# 10_-_Isolation.net
KiCad netlist of a schematic drawn in Altium Designer
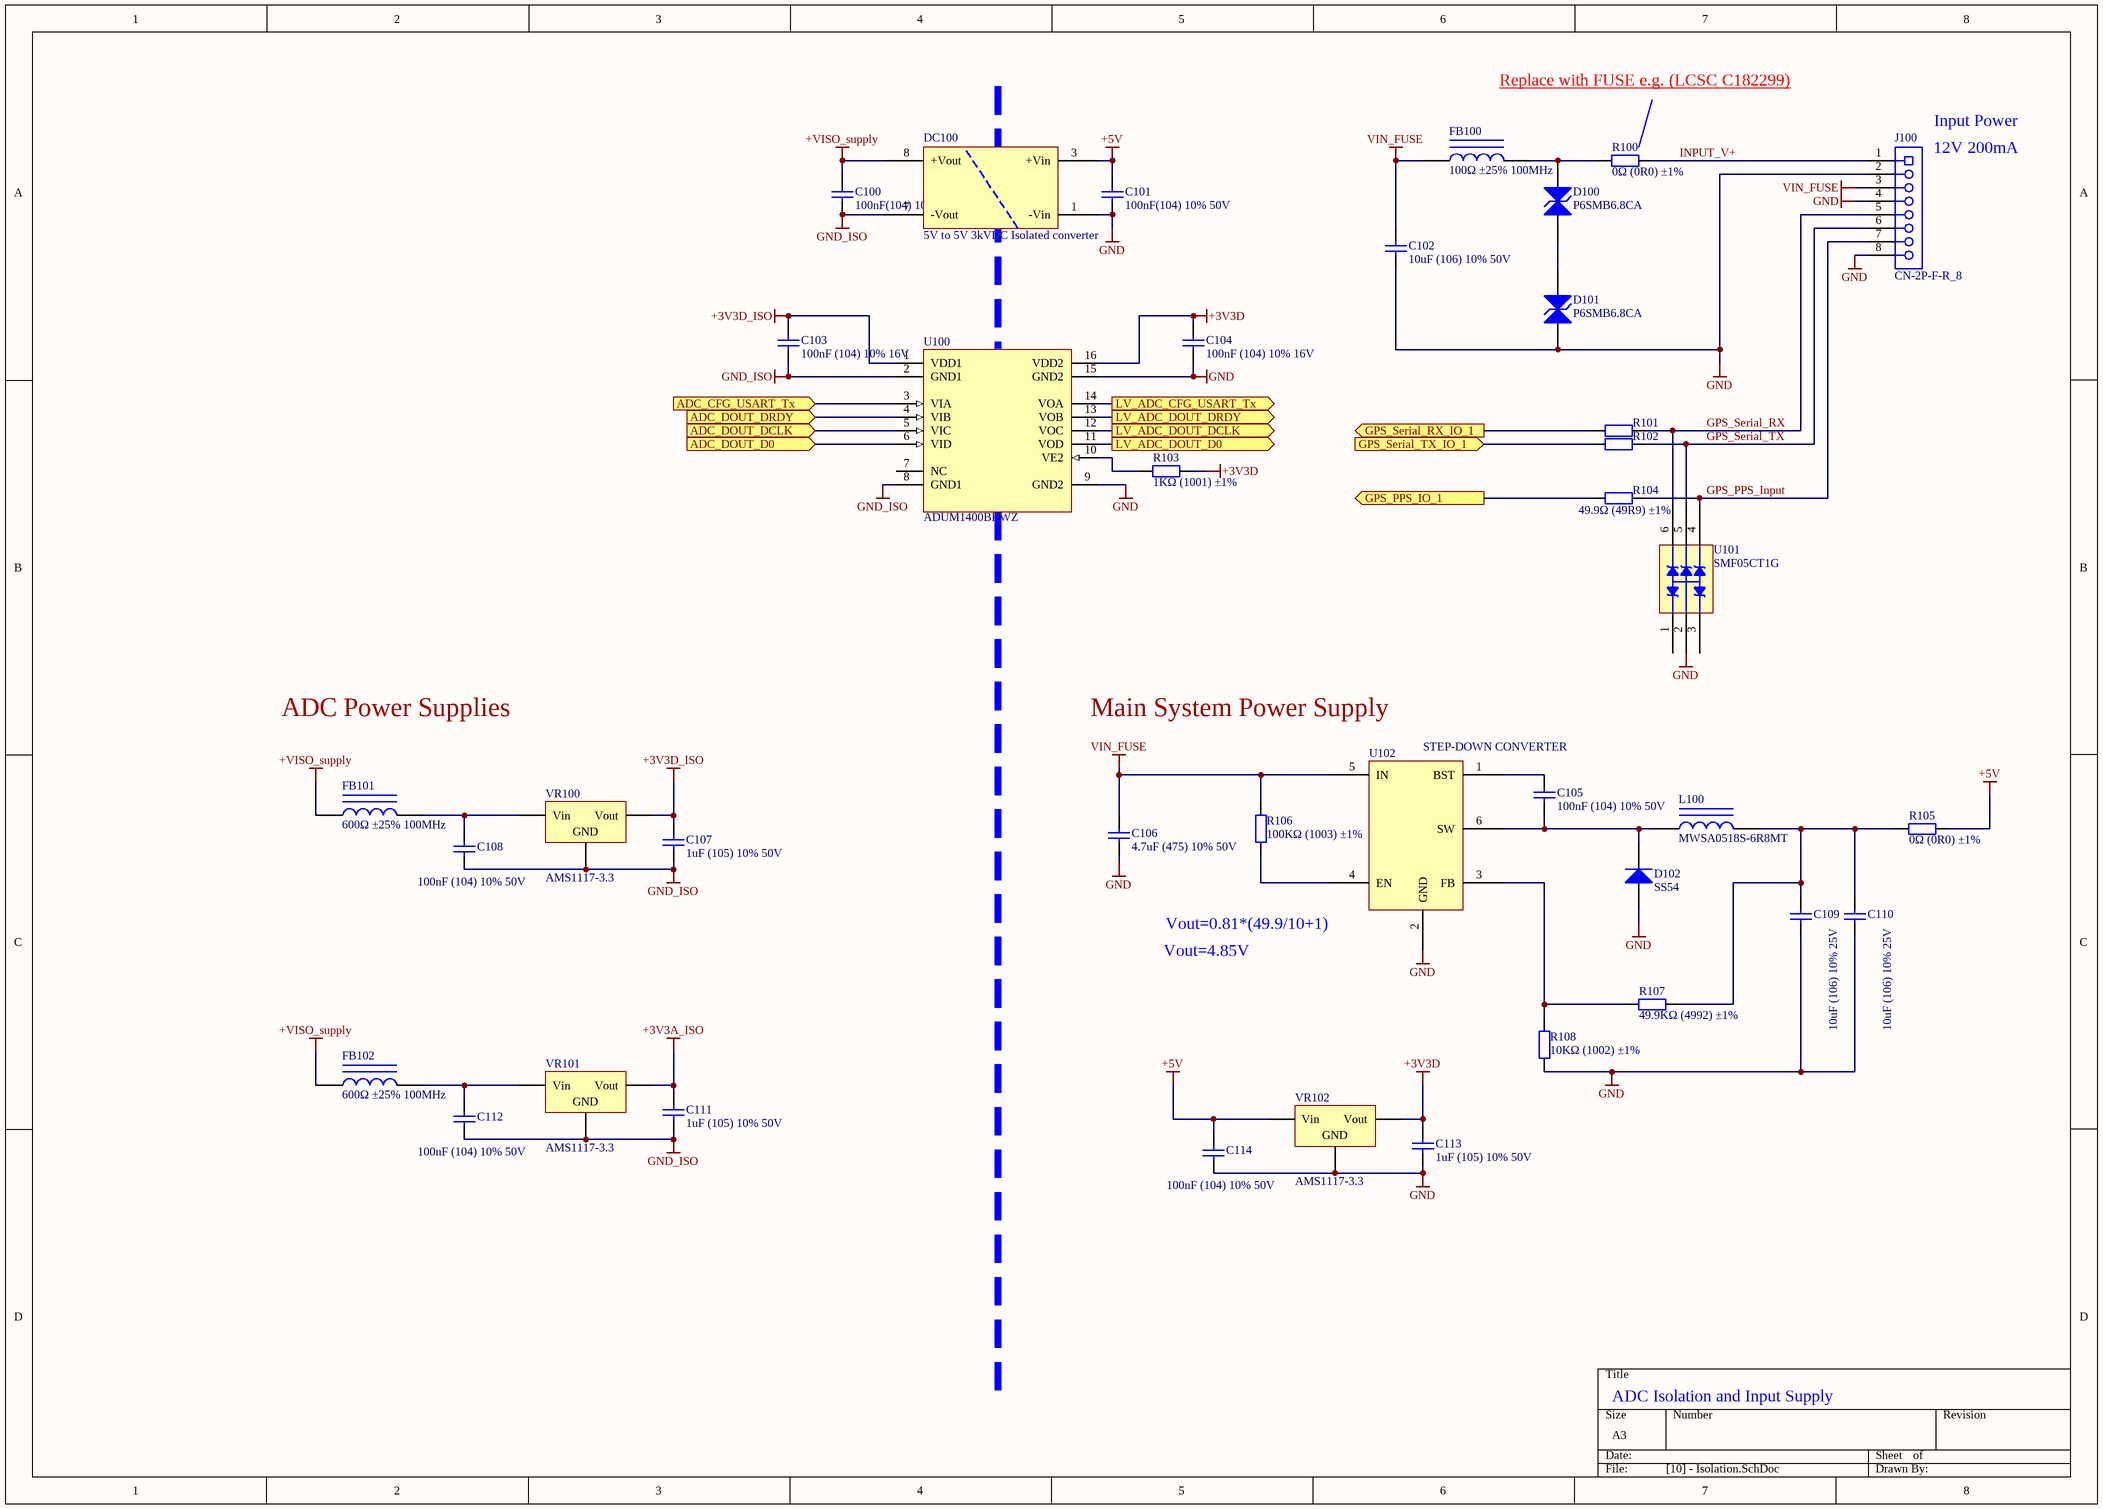
[diagram p0: [10] - Isolation.SchDoc]

(export (version "E")
  (design (tool "Eeschema 10.0.6"))
  (components
    (comp (ref "C100")
      (value "100nF(104) 10% 50V")
      (footprint "0805_C")
      (description "贴片电容")
      (libsource (lib "Cap") (part "0805 100nF(104) 10% 50V"))
    )
    (comp (ref "C101")
      (value "100nF(104) 10% 50V")
      (footprint "0805_C")
      (description "贴片电容")
      (libsource (lib "Cap") (part "0805 100nF(104) 10% 50V"))
    )
    (comp (ref "C102")
      (value "10uF (106) 10% 50V")
      (footprint "1206_C")
      (description "贴片电容")
      (libsource (lib "Cap") (part "1206 10uF (106) 10% 50V"))
    )
    (comp (ref "C103")
      (value "100nF (104) 10% 16V")
      (footprint "0402_C")
      (description "贴片电容")
      (libsource (lib "Cap") (part "0402 100nF (104) 10% 16V"))
    )
    (comp (ref "C104")
      (value "100nF (104) 10% 16V")
      (footprint "0402_C")
      (description "贴片电容")
      (libsource (lib "Cap") (part "0402 100nF (104) 10% 16V"))
    )
    (comp (ref "C105")
      (value "100nF (104) 10% 50V")
      (footprint "0603_C")
      (description "贴片电容")
      (libsource (lib "Cap") (part "0603 100nF (104) 10% 50V"))
    )
    (comp (ref "C106")
      (value "4.7uF (475) 10% 50V")
      (footprint "1206_C")
      (description "贴片电容")
      (libsource (lib "Cap") (part "1206 4.7uF (475) 10% 50V"))
    )
    (comp (ref "C107")
      (value "1uF (105) 10% 50V")
      (footprint "0603_C")
      (description "贴片电容")
      (libsource (lib "Cap") (part "0603 1uF (105) 10% 50V"))
    )
    (comp (ref "C108")
      (value "100nF (104) 10% 50V")
      (footprint "0603_C")
      (description "贴片电容")
      (libsource (lib "Cap") (part "0603 100nF (104) 10% 50V"))
    )
    (comp (ref "C109")
      (value "10uF (106) 10% 25V")
      (footprint "0805_C")
      (description "贴片电容")
      (libsource (lib "Cap") (part "0805 10uF (106) 10% 25V"))
    )
    (comp (ref "C110")
      (value "10uF (106) 10% 25V")
      (footprint "0805_C")
      (description "贴片电容")
      (libsource (lib "Cap") (part "0805 10uF (106) 10% 25V"))
    )
    (comp (ref "C111")
      (value "1uF (105) 10% 50V")
      (footprint "0603_C")
      (description "贴片电容")
      (libsource (lib "Cap") (part "0603 1uF (105) 10% 50V"))
    )
    (comp (ref "C112")
      (value "100nF (104) 10% 50V")
      (footprint "0603_C")
      (description "贴片电容")
      (libsource (lib "Cap") (part "0603 100nF (104) 10% 50V"))
    )
    (comp (ref "C113")
      (value "1uF (105) 10% 50V")
      (footprint "0603_C")
      (description "贴片电容")
      (libsource (lib "Cap") (part "0603 1uF (105) 10% 50V"))
    )
    (comp (ref "C114")
      (value "100nF (104) 10% 50V")
      (footprint "0603_C")
      (description "贴片电容")
      (libsource (lib "Cap") (part "0603 100nF (104) 10% 50V"))
    )
    (comp (ref "D100")
      (value "P6SMB6.8CA")
      (footprint "SMB(DO-214AA)_S1")
      (description "TVS")
      (libsource (lib "Diode") (part "SMB/DO-214AA P6SMB6.8CA"))
    )
    (comp (ref "D101")
      (value "P6SMB6.8CA")
      (footprint "SMB(DO-214AA)_S1")
      (description "TVS")
      (libsource (lib "Diode") (part "SMB/DO-214AA P6SMB6.8CA"))
    )
    (comp (ref "D102")
      (value "SS54")
      (footprint "SMA(DO-214AC)_S1")
      (description "二极管")
      (libsource (lib "Diode") (part "SMA(DO-214AC) SS54"))
    )
    (comp (ref "DC100")
      (value "5V to 5V 3kVDC Isolated converter")
      (footprint "NXE1S0505MC-R7")
      (description "NXE1 1W Isolated DC-DC Converter Surface Mount, Voltage in 4.5 → 5.5 V dc")
      (libsource (lib "FPGA_PMU_lib") (part "NXE1S0505MC-R7"))
    )
    (comp (ref "FB100")
      (value "100Ω ±25% 100MHz")
      (footprint "0805_L")
      (description "贴片磁珠")
      (libsource (lib "IUD") (part "0805 100Ω 25% 100MHz"))
    )
    (comp (ref "FB101")
      (value "600Ω ±25% 100MHz")
      (footprint "0805_L")
      (description "贴片磁珠")
      (libsource (lib "IUD") (part "0805 600Ω 25% 100MHz"))
    )
    (comp (ref "FB102")
      (value "600Ω ±25% 100MHz")
      (footprint "0805_L")
      (description "贴片磁珠")
      (libsource (lib "IUD") (part "0805 600Ω 25% 100MHz"))
    )
    (comp (ref "J100")
      (value "CN-2P-F-R_8")
      (footprint "PHOE-8way")
      (description "8way - 5.08 block")
      (libsource (lib "xPMU_lib") (part "CN-2P-F-R_8"))
    )
    (comp (ref "L100")
      (value "MWSA0518S-6R8MT")
      (footprint "MWSA0518")
      (description "POWER INDUCTORS SMD,5.2X5.4X1.8MM ROHS")
      (libsource (lib "FPGA_PMU_lib") (part "MWSA0518S-6R8MT"))
    )
    (comp (ref "R100")
      (value "0Ω (0R0) ±1%")
      (footprint "0603_R")
      (description "贴片电阻")
      (libsource (lib "RES") (part "0603 0Ω (0R0) 1%"))
    )
    (comp (ref "R101")
      (value "49.9Ω (49R9) ±1%")
      (footprint "0402_R")
      (description "贴片电阻")
      (libsource (lib "RES") (part "0402 49.9Ω (49R9) 1%"))
    )
    (comp (ref "R102")
      (value "49.9Ω (49R9) ±1%")
      (footprint "0402_R")
      (description "贴片电阻")
      (libsource (lib "RES") (part "0402 49.9Ω (49R9) 1%"))
    )
    (comp (ref "R103")
      (value "1KΩ (1001) ±1%")
      (footprint "0402_R")
      (description "贴片电阻")
      (libsource (lib "RES") (part "0402 1KΩ (1001) 1%"))
    )
    (comp (ref "R104")
      (value "49.9Ω (49R9) ±1%")
      (footprint "0402_R")
      (description "贴片电阻")
      (libsource (lib "RES") (part "0402 49.9Ω (49R9) 1%"))
    )
    (comp (ref "R105")
      (value "0Ω (0R0) ±1%")
      (footprint "0805_R")
      (description "贴片电阻")
      (libsource (lib "RES") (part "0805 0Ω (0R0) 1%"))
    )
    (comp (ref "R106")
      (value "100KΩ (1003) ±1%")
      (footprint "0402_R")
      (description "贴片电阻")
      (libsource (lib "RES") (part "0402 100KΩ (1003) 1%"))
    )
    (comp (ref "R107")
      (value "49.9KΩ (4992) ±1%")
      (footprint "0402_R")
      (description "贴片电阻")
      (libsource (lib "RES") (part "0402 49.9KΩ (4992) 1%"))
    )
    (comp (ref "R108")
      (value "10KΩ (1002) ±1%")
      (footprint "0402_R")
      (description "贴片电阻")
      (libsource (lib "RES") (part "0402 10KΩ (1002) 1%"))
    )
    (comp (ref "U100")
      (value "ADUM1400BRWZ")
      (footprint "ADI-RW-16_L")
      (fields (field (name "MANUFACTURER") "Analog Devices"))
      (libsource (lib "FPGA_PMU_lib") (part "ADI-ADUMX400-RX-16"))
    )
    (comp (ref "U101")
      (value "SMF05CT1G")
      (footprint "SC-70-6(SOT-363)")
      (description "TVS")
      (libsource (lib "IC") (part "SMF05CT1G_[C15879]"))
    )
    (comp (ref "U102")
      (value "STEP-DOWN CONVERTER")
      (footprint "*TSOT-23_S6")
      (description "1.2A, 24V, 1.4MHz STEP-DOWN CONVERTER IN A TSOT23-6")
      (libsource (lib "FPGA_PMU_lib") (part "MP2359"))
    )
    (comp (ref "VR100")
      (value "AMS1117-3.3")
      (footprint "SOT-223")
      (description "低压差线性稳压(LDO)")
      (libsource (lib "LDO") (part "SOT-223 AMS1117-3.3"))
    )
    (comp (ref "VR101")
      (value "AMS1117-3.3")
      (footprint "SOT-223")
      (description "低压差线性稳压(LDO)")
      (libsource (lib "LDO") (part "SOT-223 AMS1117-3.3"))
    )
    (comp (ref "VR102")
      (value "AMS1117-3.3")
      (footprint "SOT-223")
      (description "低压差线性稳压(LDO)")
      (libsource (lib "LDO") (part "SOT-223 AMS1117-3.3"))
    )
  )
  (nets
    (net (code "1") (name "+3V3A_ISO") (class "Default")
      (node (ref "C111") (pin "2") (pinfunction "2_2") (pintype "passive"))
      (node (ref "VR101") (pin "2") (pinfunction "Vout_2") (pintype "passive"))
    )
    (net (code "2") (name "+3V3D") (class "Default")
      (node (ref "C104") (pin "2") (pinfunction "2_2") (pintype "passive"))
      (node (ref "C113") (pin "2") (pinfunction "2_2") (pintype "passive"))
      (node (ref "R103") (pin "2") (pinfunction "2_2") (pintype "passive"))
      (node (ref "U100") (pin "16") (pinfunction "VDD2_16") (pintype "power_in"))
      (node (ref "VR102") (pin "2") (pinfunction "Vout_2") (pintype "passive"))
    )
    (net (code "3") (name "+3V3D_ISO") (class "Default")
      (node (ref "C103") (pin "2") (pinfunction "2_2") (pintype "passive"))
      (node (ref "C107") (pin "2") (pinfunction "2_2") (pintype "passive"))
      (node (ref "U100") (pin "1") (pinfunction "VDD1_1") (pintype "power_in"))
      (node (ref "VR100") (pin "2") (pinfunction "Vout_2") (pintype "passive"))
    )
    (net (code "4") (name "+5V") (class "Default")
      (node (ref "C101") (pin "2") (pinfunction "2_2") (pintype "passive"))
      (node (ref "C114") (pin "2") (pinfunction "2_2") (pintype "passive"))
      (node (ref "DC100") (pin "3") (pinfunction "+Vin_3") (pintype "passive"))
      (node (ref "R105") (pin "2") (pinfunction "2_2") (pintype "passive"))
      (node (ref "VR102") (pin "3") (pinfunction "Vin_3") (pintype "passive"))
    )
    (net (code "5") (name "+VISO_supply") (class "Default")
      (node (ref "C100") (pin "2") (pinfunction "2_2") (pintype "passive"))
      (node (ref "DC100") (pin "8") (pinfunction "+Vout_8") (pintype "passive"))
      (node (ref "FB101") (pin "1") (pinfunction "1_1") (pintype "passive"))
      (node (ref "FB102") (pin "1") (pinfunction "1_1") (pintype "passive"))
    )
    (net (code "6") (name "/ADC_CFG_USART_Tx") (class "Default")
      (node (ref "U100") (pin "3") (pinfunction "VIA_3") (pintype "input"))
    )
    (net (code "7") (name "/ADC_DOUT_D0") (class "Default")
      (node (ref "U100") (pin "6") (pinfunction "VID_6") (pintype "input"))
    )
    (net (code "8") (name "/ADC_DOUT_DCLK") (class "Default")
      (node (ref "U100") (pin "5") (pinfunction "VIC_5") (pintype "input"))
    )
    (net (code "9") (name "/ADC_DOUT_DRDY") (class "Default")
      (node (ref "U100") (pin "4") (pinfunction "VIB_4") (pintype "input"))
    )
    (net (code "10") (name "/GPS_PPS_IO_1") (class "Default")
      (node (ref "R104") (pin "1") (pinfunction "1_1") (pintype "passive"))
    )
    (net (code "11") (name "/GPS_PPS_Input") (class "Default")
      (node (ref "J100") (pin "7") (pinfunction "7_7") (pintype "passive"))
      (node (ref "R104") (pin "2") (pinfunction "2_2") (pintype "passive"))
      (node (ref "U101") (pin "4") (pinfunction "4_4") (pintype "passive"))
    )
    (net (code "12") (name "/GPS_Serial_RX") (class "Default")
      (node (ref "J100") (pin "5") (pinfunction "5_5") (pintype "passive"))
      (node (ref "R101") (pin "2") (pinfunction "2_2") (pintype "passive"))
      (node (ref "U101") (pin "6") (pinfunction "6_6") (pintype "passive"))
    )
    (net (code "13") (name "/GPS_Serial_RX_IO_1") (class "Default")
      (node (ref "R101") (pin "1") (pinfunction "1_1") (pintype "passive"))
    )
    (net (code "14") (name "/GPS_Serial_TX") (class "Default")
      (node (ref "J100") (pin "6") (pinfunction "6_6") (pintype "passive"))
      (node (ref "R102") (pin "2") (pinfunction "2_2") (pintype "passive"))
      (node (ref "U101") (pin "5") (pinfunction "5_5") (pintype "passive"))
    )
    (net (code "15") (name "/GPS_Serial_TX_IO_1") (class "Default")
      (node (ref "R102") (pin "1") (pinfunction "1_1") (pintype "passive"))
    )
    (net (code "16") (name "/INPUT_V+") (class "Default")
      (node (ref "J100") (pin "1") (pinfunction "1_1") (pintype "passive"))
      (node (ref "R100") (pin "2") (pinfunction "2_2") (pintype "passive"))
    )
    (net (code "17") (name "/LV_ADC_CFG_USART_Tx") (class "Default")
      (node (ref "U100") (pin "14") (pinfunction "VOA_14") (pintype "tri_state"))
    )
    (net (code "18") (name "/LV_ADC_DOUT_D0") (class "Default")
      (node (ref "U100") (pin "11") (pinfunction "VOD_11") (pintype "tri_state"))
    )
    (net (code "19") (name "/LV_ADC_DOUT_DCLK") (class "Default")
      (node (ref "U100") (pin "12") (pinfunction "VOC_12") (pintype "tri_state"))
    )
    (net (code "20") (name "/LV_ADC_DOUT_DRDY") (class "Default")
      (node (ref "U100") (pin "13") (pinfunction "VOB_13") (pintype "tri_state"))
    )
    (net (code "21") (name "GND") (class "Default")
      (node (ref "C101") (pin "1") (pinfunction "1_1") (pintype "passive"))
      (node (ref "C102") (pin "1") (pinfunction "1_1") (pintype "passive"))
      (node (ref "C104") (pin "1") (pinfunction "1_1") (pintype "passive"))
      (node (ref "C106") (pin "1") (pinfunction "1_1") (pintype "passive"))
      (node (ref "C109") (pin "1") (pinfunction "1_1") (pintype "passive"))
      (node (ref "C110") (pin "1") (pinfunction "1_1") (pintype "passive"))
      (node (ref "C113") (pin "1") (pinfunction "1_1") (pintype "passive"))
      (node (ref "C114") (pin "1") (pinfunction "1_1") (pintype "passive"))
      (node (ref "D101") (pin "1") (pinfunction "A_1") (pintype "passive"))
      (node (ref "D102") (pin "1") (pinfunction "A_1") (pintype "passive"))
      (node (ref "DC100") (pin "1") (pinfunction "-Vin_1") (pintype "passive"))
      (node (ref "J100") (pin "2") (pinfunction "2_2") (pintype "passive"))
      (node (ref "J100") (pin "4") (pinfunction "4_4") (pintype "passive"))
      (node (ref "J100") (pin "8") (pinfunction "8_8") (pintype "passive"))
      (node (ref "R108") (pin "2") (pinfunction "2_2") (pintype "passive"))
      (node (ref "U100") (pin "15") (pinfunction "GND2_15") (pintype "power_in"))
      (node (ref "U100") (pin "9") (pinfunction "GND2_9") (pintype "power_in"))
      (node (ref "U101") (pin "2") (pinfunction "2_2") (pintype "passive"))
      (node (ref "U102") (pin "2") (pinfunction "GND_2") (pintype "passive"))
      (node (ref "VR102") (pin "1") (pinfunction "GND_1") (pintype "passive"))
    )
    (net (code "22") (name "GND_ISO") (class "Default")
      (node (ref "C100") (pin "1") (pinfunction "1_1") (pintype "passive"))
      (node (ref "C103") (pin "1") (pinfunction "1_1") (pintype "passive"))
      (node (ref "C107") (pin "1") (pinfunction "1_1") (pintype "passive"))
      (node (ref "C108") (pin "1") (pinfunction "1_1") (pintype "passive"))
      (node (ref "C111") (pin "1") (pinfunction "1_1") (pintype "passive"))
      (node (ref "C112") (pin "1") (pinfunction "1_1") (pintype "passive"))
      (node (ref "DC100") (pin "7") (pinfunction "-Vout_7") (pintype "passive"))
      (node (ref "U100") (pin "2") (pinfunction "GND1_2") (pintype "power_in"))
      (node (ref "U100") (pin "8") (pinfunction "GND1_8") (pintype "power_in"))
      (node (ref "VR100") (pin "1") (pinfunction "GND_1") (pintype "passive"))
      (node (ref "VR101") (pin "1") (pinfunction "GND_1") (pintype "passive"))
    )
    (net (code "23") (name "Net-(C109-Pad2)") (class "Default")
      (node (ref "C109") (pin "2") (pinfunction "2_2") (pintype "passive"))
      (node (ref "C110") (pin "2") (pinfunction "2_2") (pintype "passive"))
      (node (ref "L100") (pin "2") (pinfunction "2_2") (pintype "power_in"))
      (node (ref "R105") (pin "1") (pinfunction "1_1") (pintype "passive"))
      (node (ref "R107") (pin "2") (pinfunction "2_2") (pintype "passive"))
    )
    (net (code "24") (name "Net-(D100-A)") (class "Default")
      (node (ref "D100") (pin "1") (pinfunction "A_1") (pintype "passive"))
      (node (ref "D101") (pin "2") (pinfunction "K_2") (pintype "passive"))
    )
    (net (code "25") (name "Net-(D100-K)") (class "Default")
      (node (ref "D100") (pin "2") (pinfunction "K_2") (pintype "passive"))
      (node (ref "FB100") (pin "2") (pinfunction "2_2") (pintype "passive"))
      (node (ref "R100") (pin "1") (pinfunction "1_1") (pintype "passive"))
    )
    (net (code "26") (name "Net-(D102-K)") (class "Default")
      (node (ref "C105") (pin "1") (pinfunction "1_1") (pintype "passive"))
      (node (ref "D102") (pin "2") (pinfunction "K_2") (pintype "passive"))
      (node (ref "L100") (pin "1") (pinfunction "1_1") (pintype "power_in"))
      (node (ref "U102") (pin "6") (pinfunction "SW_6") (pintype "passive"))
    )
    (net (code "27") (name "Net-(U100-VE2)") (class "Default")
      (node (ref "R103") (pin "1") (pinfunction "1_1") (pintype "passive"))
      (node (ref "U100") (pin "10") (pinfunction "VE2_10") (pintype "input"))
    )
    (net (code "28") (name "Net-(U102-BST)") (class "Default")
      (node (ref "C105") (pin "2") (pinfunction "2_2") (pintype "passive"))
      (node (ref "U102") (pin "1") (pinfunction "BST_1") (pintype "passive"))
    )
    (net (code "29") (name "Net-(U102-EN)") (class "Default")
      (node (ref "R106") (pin "1") (pinfunction "1_1") (pintype "passive"))
      (node (ref "U102") (pin "4") (pinfunction "EN_4") (pintype "passive"))
    )
    (net (code "30") (name "Net-(U102-FB)") (class "Default")
      (node (ref "R107") (pin "1") (pinfunction "1_1") (pintype "passive"))
      (node (ref "R108") (pin "1") (pinfunction "1_1") (pintype "passive"))
      (node (ref "U102") (pin "3") (pinfunction "FB_3") (pintype "passive"))
    )
    (net (code "31") (name "Net-(VR100-Vin)") (class "Default")
      (node (ref "C108") (pin "2") (pinfunction "2_2") (pintype "passive"))
      (node (ref "FB101") (pin "2") (pinfunction "2_2") (pintype "passive"))
      (node (ref "VR100") (pin "3") (pinfunction "Vin_3") (pintype "passive"))
    )
    (net (code "32") (name "Net-(VR101-Vin)") (class "Default")
      (node (ref "C112") (pin "2") (pinfunction "2_2") (pintype "passive"))
      (node (ref "FB102") (pin "2") (pinfunction "2_2") (pintype "passive"))
      (node (ref "VR101") (pin "3") (pinfunction "Vin_3") (pintype "passive"))
    )
    (net (code "33") (name "VIN_FUSE") (class "Default")
      (node (ref "C102") (pin "2") (pinfunction "2_2") (pintype "passive"))
      (node (ref "C106") (pin "2") (pinfunction "2_2") (pintype "passive"))
      (node (ref "FB100") (pin "1") (pinfunction "1_1") (pintype "passive"))
      (node (ref "J100") (pin "3") (pinfunction "3_3") (pintype "passive"))
      (node (ref "R106") (pin "2") (pinfunction "2_2") (pintype "passive"))
      (node (ref "U102") (pin "5") (pinfunction "IN_5") (pintype "passive"))
    )
    (net (code "34") (name "unconnected-(U100-NC-Pad7)") (class "Default")
      (node (ref "U100") (pin "7") (pinfunction "NC_7") (pintype "passive"))
    )
    (net (code "35") (name "unconnected-(U101-Pad1)") (class "Default")
      (node (ref "U101") (pin "1") (pinfunction "1_1") (pintype "passive"))
    )
    (net (code "36") (name "unconnected-(U101-Pad3)") (class "Default")
      (node (ref "U101") (pin "3") (pinfunction "3_3") (pintype "passive"))
    )
  )
)
